# AntDig.net
KiCad netlist of a schematic drawn in Altium Designer
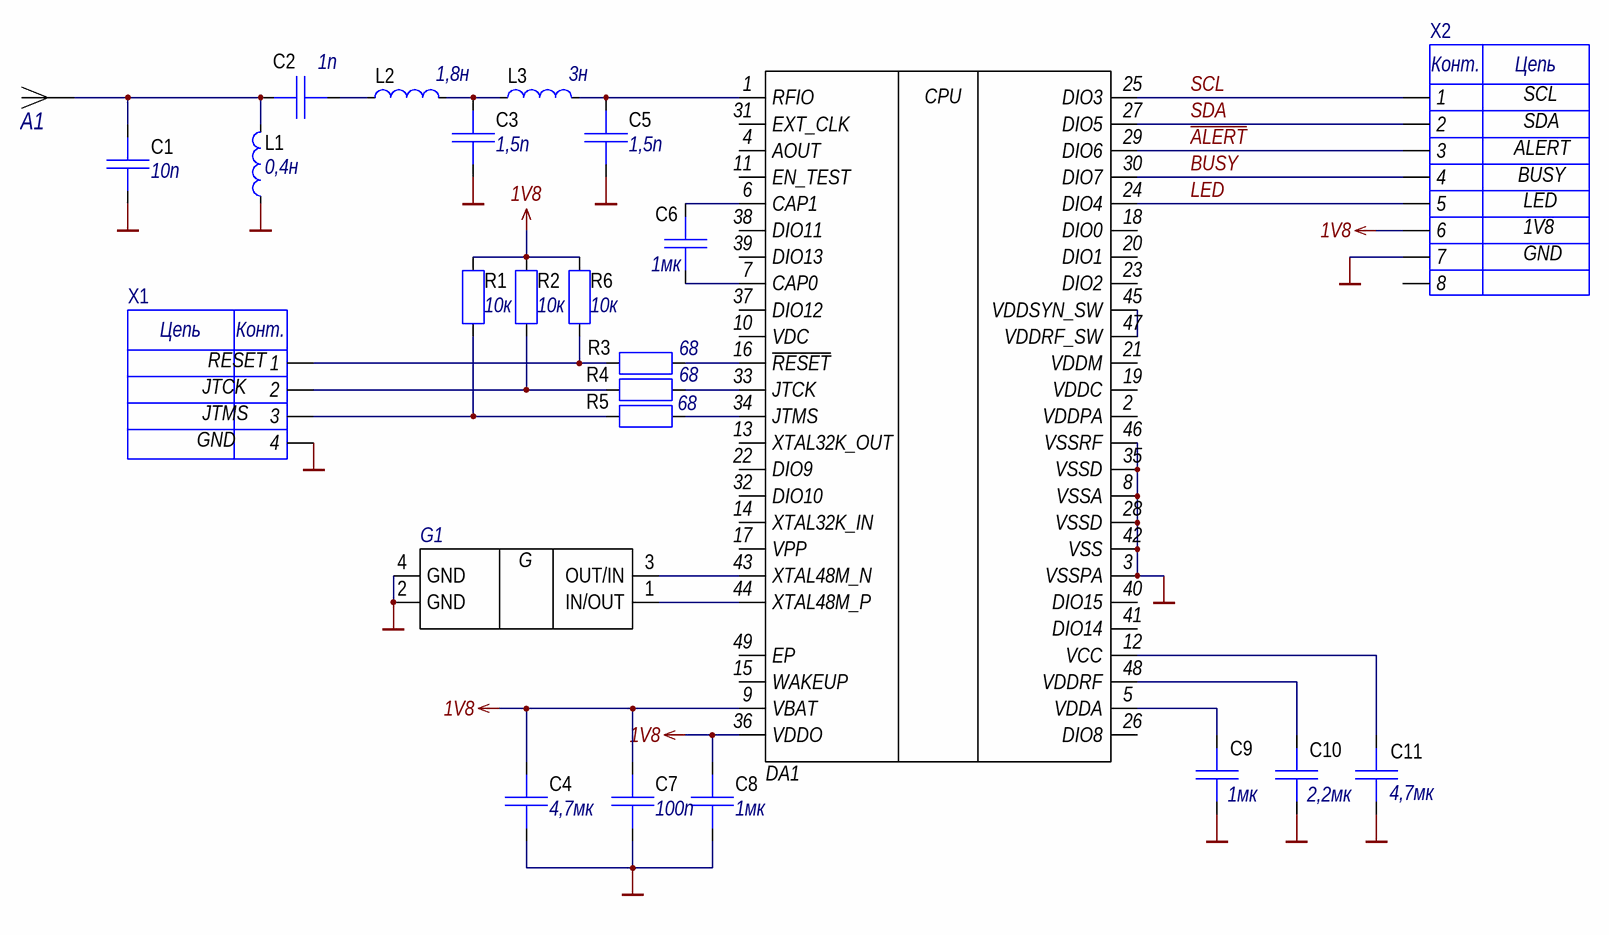
[diagram p0: AntDig.SchDoc]

(export (version "E")
  (design (tool "Eeschema 10.0.6"))
  (components
    (comp (ref "A1")
      (value "Обозначение при заказе")
      (footprint "antenna")
      (description "Описание свойств компонента")
      (libsource (lib "RSL10_SchLib") (part "antenna"))
    )
    (comp (ref "C1")
      (value "10п")
      (footprint "cap0402")
      (description "Керамический конденсатор")
      (libsource (lib "RSL10_SchLib") (part "CapCer"))
    )
    (comp (ref "C2")
      (value "1п")
      (footprint "cap0402")
      (description "Керамический конденсатор")
      (libsource (lib "RSL10_SchLib") (part "CapCer"))
    )
    (comp (ref "C3")
      (value "1,5п")
      (footprint "cap0402")
      (description "Керамический конденсатор")
      (libsource (lib "RSL10_SchLib") (part "CapCer"))
    )
    (comp (ref "C4")
      (value "4,7мк")
      (footprint "cap0402")
      (description "Керамический конденсатор")
      (libsource (lib "RSL10_SchLib") (part "CapCer"))
    )
    (comp (ref "C5")
      (value "1,5п")
      (footprint "cap0402")
      (description "Керамический конденсатор")
      (libsource (lib "RSL10_SchLib") (part "CapCer"))
    )
    (comp (ref "C6")
      (value "1мк")
      (footprint "cap0402")
      (description "Керамический конденсатор")
      (libsource (lib "RSL10_SchLib") (part "CapCer"))
    )
    (comp (ref "C7")
      (value "100п")
      (footprint "cap0402")
      (description "Керамический конденсатор")
      (libsource (lib "RSL10_SchLib") (part "CapCer"))
    )
    (comp (ref "C8")
      (value "1мк")
      (footprint "cap0402")
      (description "Керамический конденсатор")
      (libsource (lib "RSL10_SchLib") (part "CapCer"))
    )
    (comp (ref "C9")
      (value "1мк")
      (footprint "cap0402")
      (description "Керамический конденсатор")
      (libsource (lib "RSL10_SchLib") (part "CapCer"))
    )
    (comp (ref "C10")
      (value "2,2мк")
      (footprint "cap0402")
      (description "Керамический конденсатор")
      (libsource (lib "RSL10_SchLib") (part "CapCer"))
    )
    (comp (ref "C11")
      (value "4,7мк")
      (footprint "cap0402")
      (description "Керамический конденсатор")
      (libsource (lib "RSL10_SchLib") (part "CapCer"))
    )
    (comp (ref "DA1") (value "RSL10") (footprint "RSL10") (libsource (lib "RSL10_SchLib") (part "RSL10")))
    (comp (ref "G1")
      (value "Обозначение при заказе")
      (footprint "XTAL48")
      (description "ECS-480-8-47-JTN-TR")
      (libsource (lib "RSL10_SchLib") (part "XTAL48"))
    )
    (comp (ref "L1")
      (value "0,4н")
      (footprint "IND0402")
      (description "Катушка индуктивности")
      (libsource (lib "RSL10_SchLib") (part "Ind"))
    )
    (comp (ref "L2")
      (value "1,8н")
      (footprint "IND0402")
      (description "Катушка индуктивности")
      (libsource (lib "RSL10_SchLib") (part "Ind"))
    )
    (comp (ref "L3")
      (value "3н")
      (footprint "IND0402")
      (description "Катушка индуктивности")
      (libsource (lib "RSL10_SchLib") (part "Ind"))
    )
    (comp (ref "R1")
      (value "10к")
      (footprint "Res0603")
      (description "Резистор")
      (fields (field (name "TOLERANCE") "5%") (field (name "MANUFACTURER") "АЛЯР.434110.005ТУ"))
      (libsource (lib "RSL10_SchLib") (part "Res"))
    )
    (comp (ref "R2")
      (value "10к")
      (footprint "Res0603")
      (description "Резистор")
      (fields (field (name "TOLERANCE") "5%") (field (name "MANUFACTURER") "АЛЯР.434110.005ТУ"))
      (libsource (lib "RSL10_SchLib") (part "Res"))
    )
    (comp (ref "R3")
      (value "68")
      (footprint "Res0603")
      (description "Резистор")
      (fields (field (name "MANUFACTURER") "АЛЯР.434110.005ТУ"))
      (libsource (lib "") (part "Res_1"))
    )
    (comp (ref "R4")
      (value "68")
      (footprint "Res0603")
      (description "Резистор")
      (fields (field (name "MANUFACTURER") "АЛЯР.434110.005ТУ"))
      (libsource (lib "") (part "Res_1"))
    )
    (comp (ref "R5")
      (value "68")
      (footprint "Res0603")
      (description "Резистор")
      (fields (field (name "MANUFACTURER") "АЛЯР.434110.005ТУ"))
      (libsource (lib "") (part "Res_1"))
    )
    (comp (ref "R6")
      (value "10к")
      (footprint "Res0603")
      (description "Резистор")
      (fields (field (name "TOLERANCE") "5%") (field (name "MANUFACTURER") "АЛЯР.434110.005ТУ"))
      (libsource (lib "RSL10_SchLib") (part "Res"))
    )
    (comp (ref "X1")
      (value "PLS-6БСАР.430420.014ТУ")
      (footprint "PSL_4")
      (libsource (lib "RSL10_SchLib") (part "PSL4"))
    )
    (comp (ref "X2")
      (value "FFC-82328702-8")
      (footprint "FFC8")
      (libsource (lib "RSL10_SchLib") (part "FFC8"))
    )
  )
  (nets
    (net (code "1") (name "/BUSY") (class "Default")
      (node (ref "DA1") (pin "30") (pinfunction "DIO7_30") (pintype "passive"))
      (node (ref "X2") (pin "4") (pinfunction "4_4") (pintype "passive"))
    )
    (net (code "2") (name "/LED") (class "Default")
      (node (ref "DA1") (pin "24") (pinfunction "DIO4_24") (pintype "passive"))
      (node (ref "X2") (pin "5") (pinfunction "5_5") (pintype "passive"))
    )
    (net (code "3") (name "/SCL") (class "Default")
      (node (ref "DA1") (pin "25") (pinfunction "DIO3_25") (pintype "passive"))
      (node (ref "X2") (pin "1") (pinfunction "1_1") (pintype "passive"))
    )
    (net (code "4") (name "/SDA") (class "Default")
      (node (ref "DA1") (pin "27") (pinfunction "DIO5_27") (pintype "passive"))
      (node (ref "X2") (pin "2") (pinfunction "2_2") (pintype "passive"))
    )
    (net (code "5") (name "/~{ALERT}") (class "Default")
      (node (ref "DA1") (pin "29") (pinfunction "DIO6_29") (pintype "passive"))
      (node (ref "X2") (pin "3") (pinfunction "3_3") (pintype "passive"))
    )
    (net (code "6") (name "1V8") (class "Default")
      (node (ref "C4") (pin "2") (pinfunction "2_2") (pintype "passive"))
      (node (ref "C7") (pin "2") (pinfunction "2_2") (pintype "passive"))
      (node (ref "C8") (pin "2") (pinfunction "2_2") (pintype "passive"))
      (node (ref "DA1") (pin "36") (pinfunction "VDDO_36") (pintype "passive"))
      (node (ref "DA1") (pin "9") (pinfunction "VBAT_9") (pintype "passive"))
      (node (ref "R1") (pin "1") (pinfunction "1_1") (pintype "passive"))
      (node (ref "R2") (pin "1") (pinfunction "1_1") (pintype "passive"))
      (node (ref "R6") (pin "1") (pinfunction "1_1") (pintype "passive"))
      (node (ref "X2") (pin "6") (pinfunction "6_6") (pintype "passive"))
    )
    (net (code "7") (name "GND") (class "Default")
      (node (ref "C1") (pin "1") (pinfunction "1_1") (pintype "passive"))
      (node (ref "C10") (pin "1") (pinfunction "1_1") (pintype "passive"))
      (node (ref "C11") (pin "1") (pinfunction "1_1") (pintype "passive"))
      (node (ref "C3") (pin "1") (pinfunction "1_1") (pintype "passive"))
      (node (ref "C4") (pin "1") (pinfunction "1_1") (pintype "passive"))
      (node (ref "C5") (pin "1") (pinfunction "1_1") (pintype "passive"))
      (node (ref "C7") (pin "1") (pinfunction "1_1") (pintype "passive"))
      (node (ref "C8") (pin "1") (pinfunction "1_1") (pintype "passive"))
      (node (ref "C9") (pin "1") (pinfunction "1_1") (pintype "passive"))
      (node (ref "DA1") (pin "28") (pinfunction "VSSD_28") (pintype "passive"))
      (node (ref "DA1") (pin "3") (pinfunction "VSSPA_3") (pintype "passive"))
      (node (ref "DA1") (pin "35") (pinfunction "VSSD_35") (pintype "passive"))
      (node (ref "DA1") (pin "42") (pinfunction "VSS_42") (pintype "passive"))
      (node (ref "DA1") (pin "46") (pinfunction "VSSRF_46") (pintype "passive"))
      (node (ref "DA1") (pin "8") (pinfunction "VSSA_8") (pintype "passive"))
      (node (ref "G1") (pin "2") (pinfunction "GND_2") (pintype "passive"))
      (node (ref "G1") (pin "4") (pinfunction "GND_4") (pintype "passive"))
      (node (ref "L1") (pin "1") (pinfunction "1_1") (pintype "passive"))
      (node (ref "X1") (pin "4") (pinfunction "4_4") (pintype "passive"))
      (node (ref "X2") (pin "7") (pinfunction "7_7") (pintype "passive"))
    )
    (net (code "8") (name "Net-(A1-Pad1)") (class "Default")
      (node (ref "A1") (pin "1") (pinfunction "1_1") (pintype "passive"))
      (node (ref "C1") (pin "2") (pinfunction "2_2") (pintype "passive"))
      (node (ref "C2") (pin "2") (pinfunction "2_2") (pintype "passive"))
      (node (ref "L1") (pin "2") (pinfunction "2_2") (pintype "passive"))
    )
    (net (code "9") (name "Net-(C2-Pad1)") (class "Default")
      (node (ref "C2") (pin "1") (pinfunction "1_1") (pintype "passive"))
      (node (ref "L2") (pin "1") (pinfunction "1_1") (pintype "passive"))
    )
    (net (code "10") (name "Net-(C3-Pad2)") (class "Default")
      (node (ref "C3") (pin "2") (pinfunction "2_2") (pintype "passive"))
      (node (ref "L2") (pin "2") (pinfunction "2_2") (pintype "passive"))
      (node (ref "L3") (pin "1") (pinfunction "1_1") (pintype "passive"))
    )
    (net (code "11") (name "Net-(DA1-CAP0)") (class "Default")
      (node (ref "C6") (pin "1") (pinfunction "1_1") (pintype "passive"))
      (node (ref "DA1") (pin "7") (pinfunction "CAP0_7") (pintype "passive"))
    )
    (net (code "12") (name "Net-(DA1-CAP1)") (class "Default")
      (node (ref "C6") (pin "2") (pinfunction "2_2") (pintype "passive"))
      (node (ref "DA1") (pin "6") (pinfunction "CAP1_6") (pintype "passive"))
    )
    (net (code "13") (name "Net-(DA1-JTCK)") (class "Default")
      (node (ref "DA1") (pin "33") (pinfunction "JTCK_33") (pintype "passive"))
      (node (ref "R4") (pin "1") (pinfunction "1_1") (pintype "passive"))
    )
    (net (code "14") (name "Net-(DA1-JTMS)") (class "Default")
      (node (ref "DA1") (pin "34") (pinfunction "JTMS_34") (pintype "passive"))
      (node (ref "R5") (pin "1") (pinfunction "1_1") (pintype "passive"))
    )
    (net (code "15") (name "Net-(DA1-RESET)") (class "Default")
      (node (ref "DA1") (pin "16") (pinfunction "RESET_16") (pintype "passive"))
      (node (ref "R3") (pin "1") (pinfunction "1_1") (pintype "passive"))
    )
    (net (code "16") (name "Net-(DA1-RFIO)") (class "Default")
      (node (ref "C5") (pin "2") (pinfunction "2_2") (pintype "passive"))
      (node (ref "DA1") (pin "1") (pinfunction "RFIO_1") (pintype "passive"))
      (node (ref "L3") (pin "2") (pinfunction "2_2") (pintype "passive"))
    )
    (net (code "17") (name "Net-(DA1-VCC)") (class "Default")
      (node (ref "C11") (pin "2") (pinfunction "2_2") (pintype "passive"))
      (node (ref "DA1") (pin "12") (pinfunction "VCC_12") (pintype "passive"))
    )
    (net (code "18") (name "Net-(DA1-VDDA)") (class "Default")
      (node (ref "C9") (pin "2") (pinfunction "2_2") (pintype "passive"))
      (node (ref "DA1") (pin "5") (pinfunction "VDDA_5") (pintype "passive"))
    )
    (net (code "19") (name "Net-(DA1-VDDRF)") (class "Default")
      (node (ref "C10") (pin "2") (pinfunction "2_2") (pintype "passive"))
      (node (ref "DA1") (pin "48") (pinfunction "VDDRF_48") (pintype "passive"))
    )
    (net (code "20") (name "Net-(DA1-VDDRF_SW)") (class "Default")
      (node (ref "DA1") (pin "45") (pinfunction "VDDSYN_SW_45") (pintype "passive"))
      (node (ref "DA1") (pin "47") (pinfunction "VDDRF_SW_47") (pintype "passive"))
    )
    (net (code "21") (name "Net-(DA1-XTAL48M_N)") (class "Default")
      (node (ref "DA1") (pin "43") (pinfunction "XTAL48M_N_43") (pintype "passive"))
      (node (ref "G1") (pin "3") (pinfunction "OUT/IN_3") (pintype "passive"))
    )
    (net (code "22") (name "Net-(DA1-XTAL48M_P)") (class "Default")
      (node (ref "DA1") (pin "44") (pinfunction "XTAL48M_P_44") (pintype "passive"))
      (node (ref "G1") (pin "1") (pinfunction "IN/OUT_1") (pintype "passive"))
    )
    (net (code "23") (name "Net-(R1-Pad2)") (class "Default")
      (node (ref "R1") (pin "2") (pinfunction "2_2") (pintype "passive"))
      (node (ref "R5") (pin "2") (pinfunction "2_2") (pintype "passive"))
      (node (ref "X1") (pin "3") (pinfunction "3_3") (pintype "passive"))
    )
    (net (code "24") (name "Net-(R2-Pad2)") (class "Default")
      (node (ref "R2") (pin "2") (pinfunction "2_2") (pintype "passive"))
      (node (ref "R4") (pin "2") (pinfunction "2_2") (pintype "passive"))
      (node (ref "X1") (pin "2") (pinfunction "2_2") (pintype "passive"))
    )
    (net (code "25") (name "Net-(R3-Pad2)") (class "Default")
      (node (ref "R3") (pin "2") (pinfunction "2_2") (pintype "passive"))
      (node (ref "R6") (pin "2") (pinfunction "2_2") (pintype "passive"))
      (node (ref "X1") (pin "1") (pinfunction "1_1") (pintype "passive"))
    )
    (net (code "26") (name "unconnected-(DA1-AOUT-Pad4)") (class "Default")
      (node (ref "DA1") (pin "4") (pinfunction "AOUT_4") (pintype "passive"))
    )
    (net (code "27") (name "unconnected-(DA1-DIO0-Pad18)") (class "Default")
      (node (ref "DA1") (pin "18") (pinfunction "DIO0_18") (pintype "passive"))
    )
    (net (code "28") (name "unconnected-(DA1-DIO1-Pad20)") (class "Default")
      (node (ref "DA1") (pin "20") (pinfunction "DIO1_20") (pintype "passive"))
    )
    (net (code "29") (name "unconnected-(DA1-DIO2-Pad23)") (class "Default")
      (node (ref "DA1") (pin "23") (pinfunction "DIO2_23") (pintype "passive"))
    )
    (net (code "30") (name "unconnected-(DA1-DIO8-Pad26)") (class "Default")
      (node (ref "DA1") (pin "26") (pinfunction "DIO8_26") (pintype "passive"))
    )
    (net (code "31") (name "unconnected-(DA1-DIO9-Pad22)") (class "Default")
      (node (ref "DA1") (pin "22") (pinfunction "DIO9_22") (pintype "passive"))
    )
    (net (code "32") (name "unconnected-(DA1-DIO10-Pad32)") (class "Default")
      (node (ref "DA1") (pin "32") (pinfunction "DIO10_32") (pintype "passive"))
    )
    (net (code "33") (name "unconnected-(DA1-DIO11-Pad38)") (class "Default")
      (node (ref "DA1") (pin "38") (pinfunction "DIO11_38") (pintype "passive"))
    )
    (net (code "34") (name "unconnected-(DA1-DIO12-Pad37)") (class "Default")
      (node (ref "DA1") (pin "37") (pinfunction "DIO12_37") (pintype "passive"))
    )
    (net (code "35") (name "unconnected-(DA1-DIO13-Pad39)") (class "Default")
      (node (ref "DA1") (pin "39") (pinfunction "DIO13_39") (pintype "passive"))
    )
    (net (code "36") (name "unconnected-(DA1-DIO14-Pad41)") (class "Default")
      (node (ref "DA1") (pin "41") (pinfunction "DIO14_41") (pintype "passive"))
    )
    (net (code "37") (name "unconnected-(DA1-DIO15-Pad40)") (class "Default")
      (node (ref "DA1") (pin "40") (pinfunction "DIO15_40") (pintype "passive"))
    )
    (net (code "38") (name "unconnected-(DA1-EN_TEST-Pad11)") (class "Default")
      (node (ref "DA1") (pin "11") (pinfunction "EN_TEST_11") (pintype "passive"))
    )
    (net (code "39") (name "unconnected-(DA1-EP-Pad49)") (class "Default")
      (node (ref "DA1") (pin "49") (pinfunction "EP_49") (pintype "passive"))
    )
    (net (code "40") (name "unconnected-(DA1-EXT_CLK-Pad31)") (class "Default")
      (node (ref "DA1") (pin "31") (pinfunction "EXT_CLK_31") (pintype "passive"))
    )
    (net (code "41") (name "unconnected-(DA1-VDC-Pad10)") (class "Default")
      (node (ref "DA1") (pin "10") (pinfunction "VDC_10") (pintype "passive"))
    )
    (net (code "42") (name "unconnected-(DA1-VDDC-Pad19)") (class "Default")
      (node (ref "DA1") (pin "19") (pinfunction "VDDC_19") (pintype "passive"))
    )
    (net (code "43") (name "unconnected-(DA1-VDDM-Pad21)") (class "Default")
      (node (ref "DA1") (pin "21") (pinfunction "VDDM_21") (pintype "passive"))
    )
    (net (code "44") (name "unconnected-(DA1-VDDPA-Pad2)") (class "Default")
      (node (ref "DA1") (pin "2") (pinfunction "VDDPA_2") (pintype "passive"))
    )
    (net (code "45") (name "unconnected-(DA1-VPP-Pad17)") (class "Default")
      (node (ref "DA1") (pin "17") (pinfunction "VPP_17") (pintype "passive"))
    )
    (net (code "46") (name "unconnected-(DA1-WAKEUP-Pad15)") (class "Default")
      (node (ref "DA1") (pin "15") (pinfunction "WAKEUP_15") (pintype "passive"))
    )
    (net (code "47") (name "unconnected-(DA1-XTAL32K_IN-Pad14)") (class "Default")
      (node (ref "DA1") (pin "14") (pinfunction "XTAL32K_IN_14") (pintype "passive"))
    )
    (net (code "48") (name "unconnected-(DA1-XTAL32K_OUT-Pad13)") (class "Default")
      (node (ref "DA1") (pin "13") (pinfunction "XTAL32K_OUT_13") (pintype "passive"))
    )
    (net (code "49") (name "unconnected-(X2-Pad8)") (class "Default")
      (node (ref "X2") (pin "8") (pinfunction "8_8") (pintype "passive"))
    )
  )
)
